# switchBoard.net
KiCad netlist of a schematic drawn in EAGLE
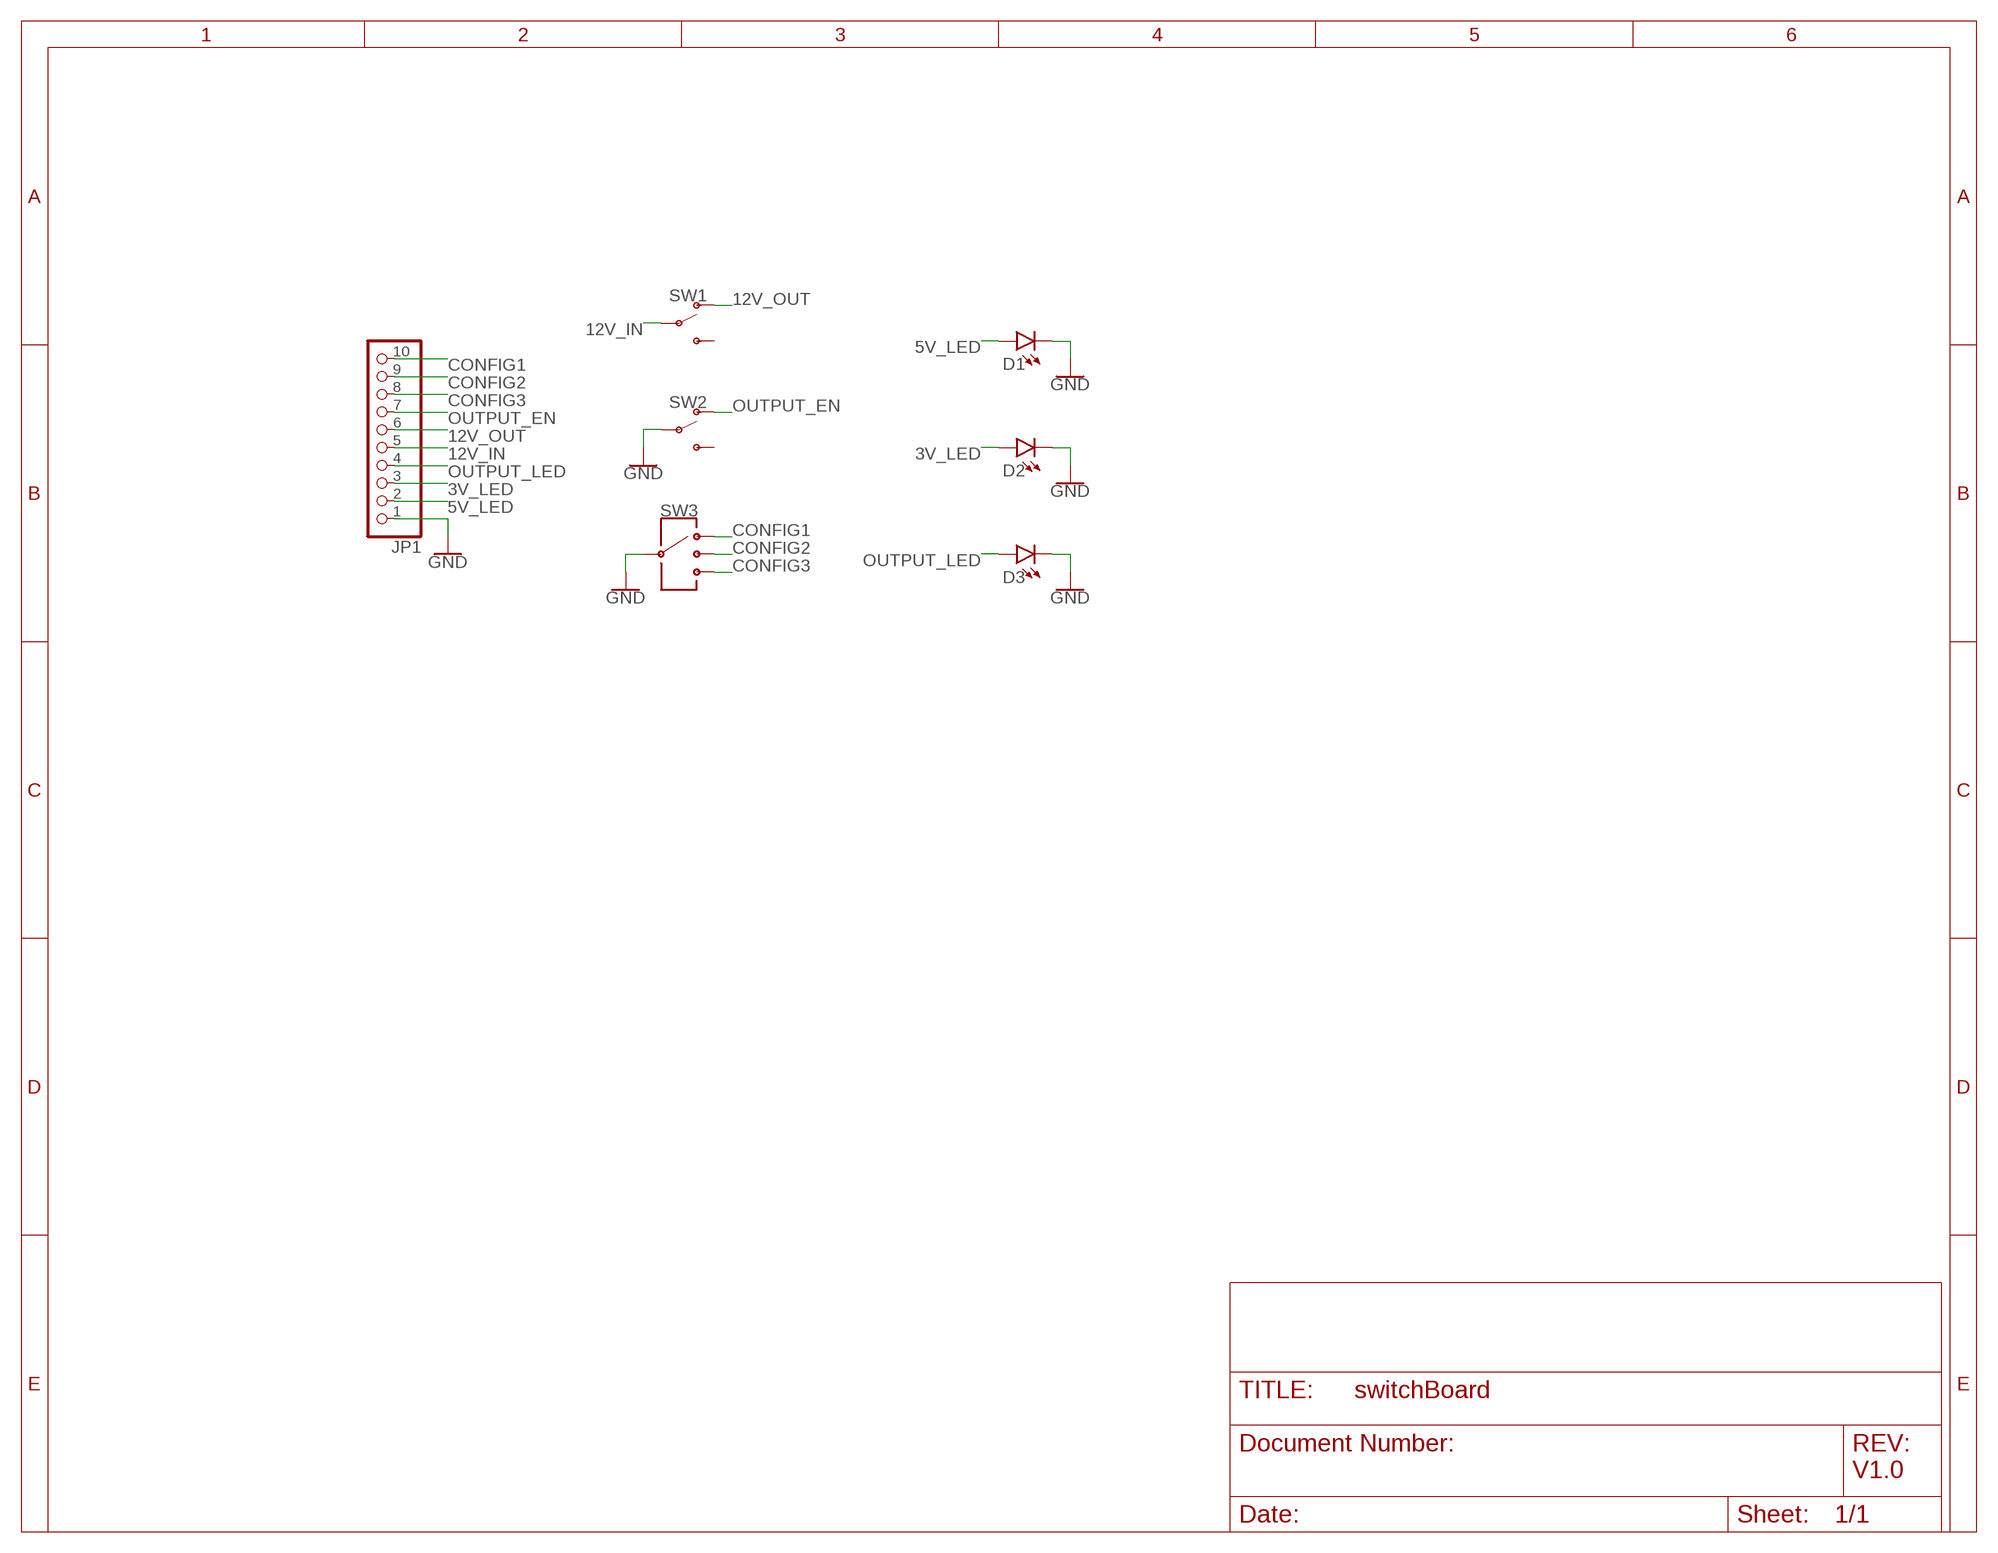
[diagram p0: schematic, sheet 1]

(export (version "E")
  (design (tool "Eeschema 10.0.6"))
  (components
    (comp (ref "D1")
      (value "LED5MM")
      (footprint "eagle-import:LED_5MM")
      (libsource (lib "eagle-import") (part "LED5MM"))
    )
    (comp (ref "D2")
      (value "LED5MM")
      (footprint "eagle-import:LED_5MM")
      (libsource (lib "eagle-import") (part "LED5MM"))
    )
    (comp (ref "D3")
      (value "LED5MM")
      (footprint "eagle-import:LED_5MM")
      (libsource (lib "eagle-import") (part "LED5MM"))
    )
    (comp (ref "JP1")
      (value "PINHD-1X10")
      (footprint "eagle-import:1X10")
      (libsource (lib "eagle-import") (part "PINHD-1X10"))
    )
    (comp (ref "SW1")
      (value "SPDT")
      (footprint "eagle-import:SPDT")
      (libsource (lib "eagle-import") (part "SPDT"))
    )
    (comp (ref "SW2")
      (value "SPDT")
      (footprint "eagle-import:SPDT")
      (libsource (lib "eagle-import") (part "SPDT"))
    )
    (comp (ref "SW3")
      (value "SP3T")
      (footprint "eagle-import:SP3T")
      (libsource (lib "eagle-import") (part "SP3T"))
    )
  )
  (nets
    (net (code "1") (name "/3V_LED") (class "Default")
      (node (ref "D2") (pin "A") (pinfunction "A_A") (pintype "passive"))
      (node (ref "JP1") (pin "3") (pinfunction "3_3") (pintype "passive"))
    )
    (net (code "2") (name "/5V_LED") (class "Default")
      (node (ref "D1") (pin "A") (pinfunction "A_A") (pintype "passive"))
      (node (ref "JP1") (pin "2") (pinfunction "2_2") (pintype "passive"))
    )
    (net (code "3") (name "/12V_IN") (class "Default")
      (node (ref "JP1") (pin "5") (pinfunction "5_5") (pintype "passive"))
      (node (ref "SW1") (pin "2") (pinfunction "P_2") (pintype "passive"))
    )
    (net (code "4") (name "/12V_OUT") (class "Default")
      (node (ref "JP1") (pin "6") (pinfunction "6_6") (pintype "passive"))
      (node (ref "SW1") (pin "1") (pinfunction "O_1") (pintype "passive"))
    )
    (net (code "5") (name "/CONFIG1") (class "Default")
      (node (ref "JP1") (pin "10") (pinfunction "10_10") (pintype "passive"))
      (node (ref "SW3") (pin "P$1") (pinfunction "1_P$1") (pintype "bidirectional"))
    )
    (net (code "6") (name "/CONFIG2") (class "Default")
      (node (ref "JP1") (pin "9") (pinfunction "9_9") (pintype "passive"))
      (node (ref "SW3") (pin "P$3") (pinfunction "3_P$3") (pintype "bidirectional"))
    )
    (net (code "7") (name "/CONFIG3") (class "Default")
      (node (ref "JP1") (pin "8") (pinfunction "8_8") (pintype "passive"))
      (node (ref "SW3") (pin "P$4") (pinfunction "4_P$4") (pintype "bidirectional"))
    )
    (net (code "8") (name "/OUTPUT_EN") (class "Default")
      (node (ref "JP1") (pin "7") (pinfunction "7_7") (pintype "passive"))
      (node (ref "SW2") (pin "1") (pinfunction "O_1") (pintype "passive"))
    )
    (net (code "9") (name "/OUTPUT_LED") (class "Default")
      (node (ref "D3") (pin "A") (pinfunction "A_A") (pintype "passive"))
      (node (ref "JP1") (pin "4") (pinfunction "4_4") (pintype "passive"))
    )
    (net (code "10") (name "GND") (class "Default")
      (node (ref "D1") (pin "K") (pinfunction "C_K") (pintype "passive"))
      (node (ref "D2") (pin "K") (pinfunction "C_K") (pintype "passive"))
      (node (ref "D3") (pin "K") (pinfunction "C_K") (pintype "passive"))
      (node (ref "JP1") (pin "1") (pinfunction "1_1") (pintype "passive"))
      (node (ref "SW2") (pin "2") (pinfunction "P_2") (pintype "passive"))
      (node (ref "SW3") (pin "P$2") (pinfunction "2_P$2") (pintype "bidirectional"))
    )
    (net (code "11") (name "unconnected-(SW1-S-Pad3)") (class "Default")
      (node (ref "SW1") (pin "3") (pinfunction "S_3") (pintype "passive"))
    )
    (net (code "12") (name "unconnected-(SW2-S-Pad3)") (class "Default")
      (node (ref "SW2") (pin "3") (pinfunction "S_3") (pintype "passive"))
    )
  )
)
